# dlp_2-channel-mixer_v1_0.net
KiCad netlist of a schematic drawn in EAGLE
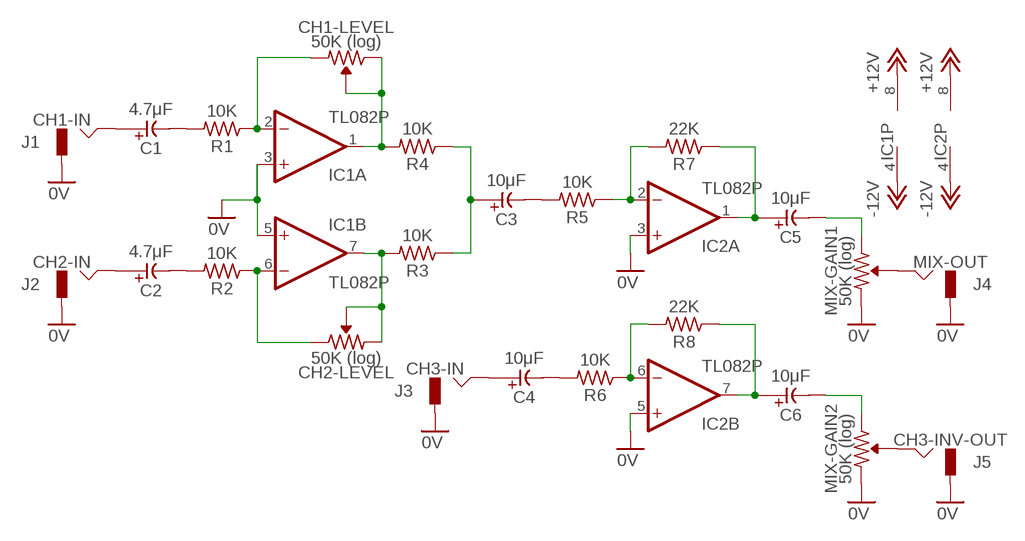
[diagram p0: schematic, sheet 1]

(export (version "E")
  (design (tool "Eeschema 10.0.6"))
  (components
    (comp (ref "C1")
      (value "4.7μF")
      (footprint "eagle-import:E2-5")
      (libsource (lib "eagle-import") (part "CE-USE2-5"))
    )
    (comp (ref "C2")
      (value "4.7μF")
      (footprint "eagle-import:E2-5")
      (libsource (lib "eagle-import") (part "CE-USE2-5"))
    )
    (comp (ref "C3")
      (value "10μF")
      (footprint "eagle-import:E2-5")
      (libsource (lib "eagle-import") (part "CE-USE2-5"))
    )
    (comp (ref "C4")
      (value "10μF")
      (footprint "eagle-import:E2-5")
      (libsource (lib "eagle-import") (part "CE-USE2-5"))
    )
    (comp (ref "C5")
      (value "10μF")
      (footprint "eagle-import:E2-5")
      (libsource (lib "eagle-import") (part "CE-USE2-5"))
    )
    (comp (ref "C6")
      (value "10μF")
      (footprint "eagle-import:E2-5")
      (libsource (lib "eagle-import") (part "CE-USE2-5"))
    )
    (comp (ref "CH1-LEVEL")
      (value "50K (log)")
      (footprint "eagle-import:R-VAR")
      (libsource (lib "eagle-import") (part "R-VAR"))
    )
    (comp (ref "CH2-LEVEL")
      (value "50K (log)")
      (footprint "eagle-import:R-VAR")
      (libsource (lib "eagle-import") (part "R-VAR"))
    )
    (comp (ref "IC1")
      (value "TL082P")
      (footprint "eagle-import:DIL08")
      (libsource (lib "eagle-import") (part "TL082P"))
    )
    (comp (ref "IC2")
      (value "TL082P")
      (footprint "eagle-import:DIL08")
      (libsource (lib "eagle-import") (part "TL082P"))
    )
    (comp (ref "J1")
      (value "CH1-IN")
      (footprint "eagle-import:JACK-M")
      (libsource (lib "eagle-import") (part "JACK-M"))
    )
    (comp (ref "J2")
      (value "CH2-IN")
      (footprint "eagle-import:JACK-M")
      (libsource (lib "eagle-import") (part "JACK-M"))
    )
    (comp (ref "J3")
      (value "CH3-IN")
      (footprint "eagle-import:JACK-M")
      (libsource (lib "eagle-import") (part "JACK-M"))
    )
    (comp (ref "J4")
      (value "MIX-OUT")
      (footprint "eagle-import:JACK-M")
      (libsource (lib "eagle-import") (part "JACK-M"))
    )
    (comp (ref "J5")
      (value "CH3-INV-OUT")
      (footprint "eagle-import:JACK-M")
      (libsource (lib "eagle-import") (part "JACK-M"))
    )
    (comp (ref "MIX-GAIN1")
      (value "50K (log)")
      (footprint "eagle-import:R-VAR")
      (libsource (lib "eagle-import") (part "R-VAR"))
    )
    (comp (ref "MIX-GAIN2")
      (value "50K (log)")
      (footprint "eagle-import:R-VAR")
      (libsource (lib "eagle-import") (part "R-VAR"))
    )
    (comp (ref "R1")
      (value "10K")
      (footprint "eagle-import:0309_10")
      (libsource (lib "eagle-import") (part "R0309/10"))
    )
    (comp (ref "R2")
      (value "10K")
      (footprint "eagle-import:0309_10")
      (libsource (lib "eagle-import") (part "R0309/10"))
    )
    (comp (ref "R3")
      (value "10K")
      (footprint "eagle-import:0309_10")
      (libsource (lib "eagle-import") (part "R0309/10"))
    )
    (comp (ref "R4")
      (value "10K")
      (footprint "eagle-import:0309_10")
      (libsource (lib "eagle-import") (part "R0309/10"))
    )
    (comp (ref "R5")
      (value "10K")
      (footprint "eagle-import:0309_10")
      (libsource (lib "eagle-import") (part "R0309/10"))
    )
    (comp (ref "R6")
      (value "10K")
      (footprint "eagle-import:0309_10")
      (libsource (lib "eagle-import") (part "R0309/10"))
    )
    (comp (ref "R7")
      (value "22K")
      (footprint "eagle-import:0309_10")
      (libsource (lib "eagle-import") (part "R0309/10"))
    )
    (comp (ref "R8")
      (value "22K")
      (footprint "eagle-import:0309_10")
      (libsource (lib "eagle-import") (part "R0309/10"))
    )
  )
  (nets
    (net (code "1") (name "+12V") (class "Default")
      (node (ref "IC1") (pin "8") (pinfunction "V+_8") (pintype "power_in"))
      (node (ref "IC2") (pin "8") (pinfunction "V+_8") (pintype "power_in"))
    )
    (net (code "2") (name "-12V") (class "Default")
      (node (ref "IC1") (pin "4") (pinfunction "V-_4") (pintype "power_in"))
      (node (ref "IC2") (pin "4") (pinfunction "V-_4") (pintype "power_in"))
    )
    (net (code "3") (name "0V") (class "Default")
      (node (ref "IC1") (pin "3") (pinfunction "+IN_3") (pintype "input"))
      (node (ref "IC1") (pin "5") (pinfunction "+IN_5") (pintype "input"))
      (node (ref "IC2") (pin "3") (pinfunction "+IN_3") (pintype "input"))
      (node (ref "IC2") (pin "5") (pinfunction "+IN_5") (pintype "input"))
      (node (ref "J1") (pin "GND") (pinfunction "GND_GND") (pintype "bidirectional"))
      (node (ref "J2") (pin "GND") (pinfunction "GND_GND") (pintype "bidirectional"))
      (node (ref "J3") (pin "GND") (pinfunction "GND_GND") (pintype "bidirectional"))
      (node (ref "J4") (pin "GND") (pinfunction "GND_GND") (pintype "bidirectional"))
      (node (ref "J5") (pin "GND") (pinfunction "GND_GND") (pintype "bidirectional"))
      (node (ref "MIX-GAIN1") (pin "R2") (pinfunction "2_R2") (pintype "passive"))
      (node (ref "MIX-GAIN2") (pin "R2") (pinfunction "2_R2") (pintype "passive"))
    )
    (net (code "4") (name "Net-(C1-Pad+)") (class "Default")
      (node (ref "C1") (pin "+") (pinfunction "+_+") (pintype "passive"))
      (node (ref "J1") (pin "HOT") (pinfunction "HOT_HOT") (pintype "bidirectional"))
    )
    (net (code "5") (name "Net-(C1-Pad-)") (class "Default")
      (node (ref "C1") (pin "-") (pinfunction "-_-") (pintype "passive"))
      (node (ref "R1") (pin "2") (pinfunction "2_2") (pintype "passive"))
    )
    (net (code "6") (name "Net-(C2-Pad+)") (class "Default")
      (node (ref "C2") (pin "+") (pinfunction "+_+") (pintype "passive"))
      (node (ref "J2") (pin "HOT") (pinfunction "HOT_HOT") (pintype "bidirectional"))
    )
    (net (code "7") (name "Net-(C2-Pad-)") (class "Default")
      (node (ref "C2") (pin "-") (pinfunction "-_-") (pintype "passive"))
      (node (ref "R2") (pin "2") (pinfunction "2_2") (pintype "passive"))
    )
    (net (code "8") (name "Net-(C3-Pad+)") (class "Default")
      (node (ref "C3") (pin "+") (pinfunction "+_+") (pintype "passive"))
      (node (ref "R3") (pin "1") (pinfunction "1_1") (pintype "passive"))
      (node (ref "R4") (pin "1") (pinfunction "1_1") (pintype "passive"))
    )
    (net (code "9") (name "Net-(C3-Pad-)") (class "Default")
      (node (ref "C3") (pin "-") (pinfunction "-_-") (pintype "passive"))
      (node (ref "R5") (pin "2") (pinfunction "2_2") (pintype "passive"))
    )
    (net (code "10") (name "Net-(C4-Pad+)") (class "Default")
      (node (ref "C4") (pin "+") (pinfunction "+_+") (pintype "passive"))
      (node (ref "J3") (pin "HOT") (pinfunction "HOT_HOT") (pintype "bidirectional"))
    )
    (net (code "11") (name "Net-(C4-Pad-)") (class "Default")
      (node (ref "C4") (pin "-") (pinfunction "-_-") (pintype "passive"))
      (node (ref "R6") (pin "2") (pinfunction "2_2") (pintype "passive"))
    )
    (net (code "12") (name "Net-(CH1-LEVEL-1)") (class "Default")
      (node (ref "CH1-LEVEL") (pin "R1") (pinfunction "1_R1") (pintype "passive"))
      (node (ref "CH1-LEVEL") (pin "VAR") (pinfunction "P$1_VAR") (pintype "passive"))
      (node (ref "IC1") (pin "1") (pinfunction "OUT_1") (pintype "output"))
      (node (ref "R4") (pin "2") (pinfunction "2_2") (pintype "passive"))
    )
    (net (code "13") (name "Net-(CH1-LEVEL-2)") (class "Default")
      (node (ref "CH1-LEVEL") (pin "R2") (pinfunction "2_R2") (pintype "passive"))
      (node (ref "IC1") (pin "2") (pinfunction "-IN_2") (pintype "input"))
      (node (ref "R1") (pin "1") (pinfunction "1_1") (pintype "passive"))
    )
    (net (code "14") (name "Net-(CH2-LEVEL-1)") (class "Default")
      (node (ref "CH2-LEVEL") (pin "R1") (pinfunction "1_R1") (pintype "passive"))
      (node (ref "IC1") (pin "6") (pinfunction "-IN_6") (pintype "input"))
      (node (ref "R2") (pin "1") (pinfunction "1_1") (pintype "passive"))
    )
    (net (code "15") (name "Net-(CH2-LEVEL-2)") (class "Default")
      (node (ref "CH2-LEVEL") (pin "R2") (pinfunction "2_R2") (pintype "passive"))
      (node (ref "CH2-LEVEL") (pin "VAR") (pinfunction "P$1_VAR") (pintype "passive"))
      (node (ref "IC1") (pin "7") (pinfunction "OUT_7") (pintype "output"))
      (node (ref "R3") (pin "2") (pinfunction "2_2") (pintype "passive"))
    )
    (net (code "16") (name "Net-(IC2A--IN)") (class "Default")
      (node (ref "IC2") (pin "2") (pinfunction "-IN_2") (pintype "input"))
      (node (ref "R5") (pin "1") (pinfunction "1_1") (pintype "passive"))
      (node (ref "R7") (pin "2") (pinfunction "2_2") (pintype "passive"))
    )
    (net (code "17") (name "Net-(IC2A-OUT)") (class "Default")
      (node (ref "C5") (pin "+") (pinfunction "+_+") (pintype "passive"))
      (node (ref "IC2") (pin "1") (pinfunction "OUT_1") (pintype "output"))
      (node (ref "R7") (pin "1") (pinfunction "1_1") (pintype "passive"))
    )
    (net (code "18") (name "Net-(IC2B--IN)") (class "Default")
      (node (ref "IC2") (pin "6") (pinfunction "-IN_6") (pintype "input"))
      (node (ref "R6") (pin "1") (pinfunction "1_1") (pintype "passive"))
      (node (ref "R8") (pin "2") (pinfunction "2_2") (pintype "passive"))
    )
    (net (code "19") (name "Net-(IC2B-OUT)") (class "Default")
      (node (ref "C6") (pin "+") (pinfunction "+_+") (pintype "passive"))
      (node (ref "IC2") (pin "7") (pinfunction "OUT_7") (pintype "output"))
      (node (ref "R8") (pin "1") (pinfunction "1_1") (pintype "passive"))
    )
    (net (code "20") (name "Net-(MIX-GAIN1-1)") (class "Default")
      (node (ref "C5") (pin "-") (pinfunction "-_-") (pintype "passive"))
      (node (ref "MIX-GAIN1") (pin "R1") (pinfunction "1_R1") (pintype "passive"))
    )
    (net (code "21") (name "Net-(MIX-GAIN1-P$1)") (class "Default")
      (node (ref "J4") (pin "HOT") (pinfunction "HOT_HOT") (pintype "bidirectional"))
      (node (ref "MIX-GAIN1") (pin "VAR") (pinfunction "P$1_VAR") (pintype "passive"))
    )
    (net (code "22") (name "Net-(MIX-GAIN2-1)") (class "Default")
      (node (ref "C6") (pin "-") (pinfunction "-_-") (pintype "passive"))
      (node (ref "MIX-GAIN2") (pin "R1") (pinfunction "1_R1") (pintype "passive"))
    )
    (net (code "23") (name "Net-(MIX-GAIN2-P$1)") (class "Default")
      (node (ref "J5") (pin "HOT") (pinfunction "HOT_HOT") (pintype "bidirectional"))
      (node (ref "MIX-GAIN2") (pin "VAR") (pinfunction "P$1_VAR") (pintype "passive"))
    )
  )
)
